# IE_ARSA_Merah_W.net
KiCad netlist of a schematic drawn in EAGLE
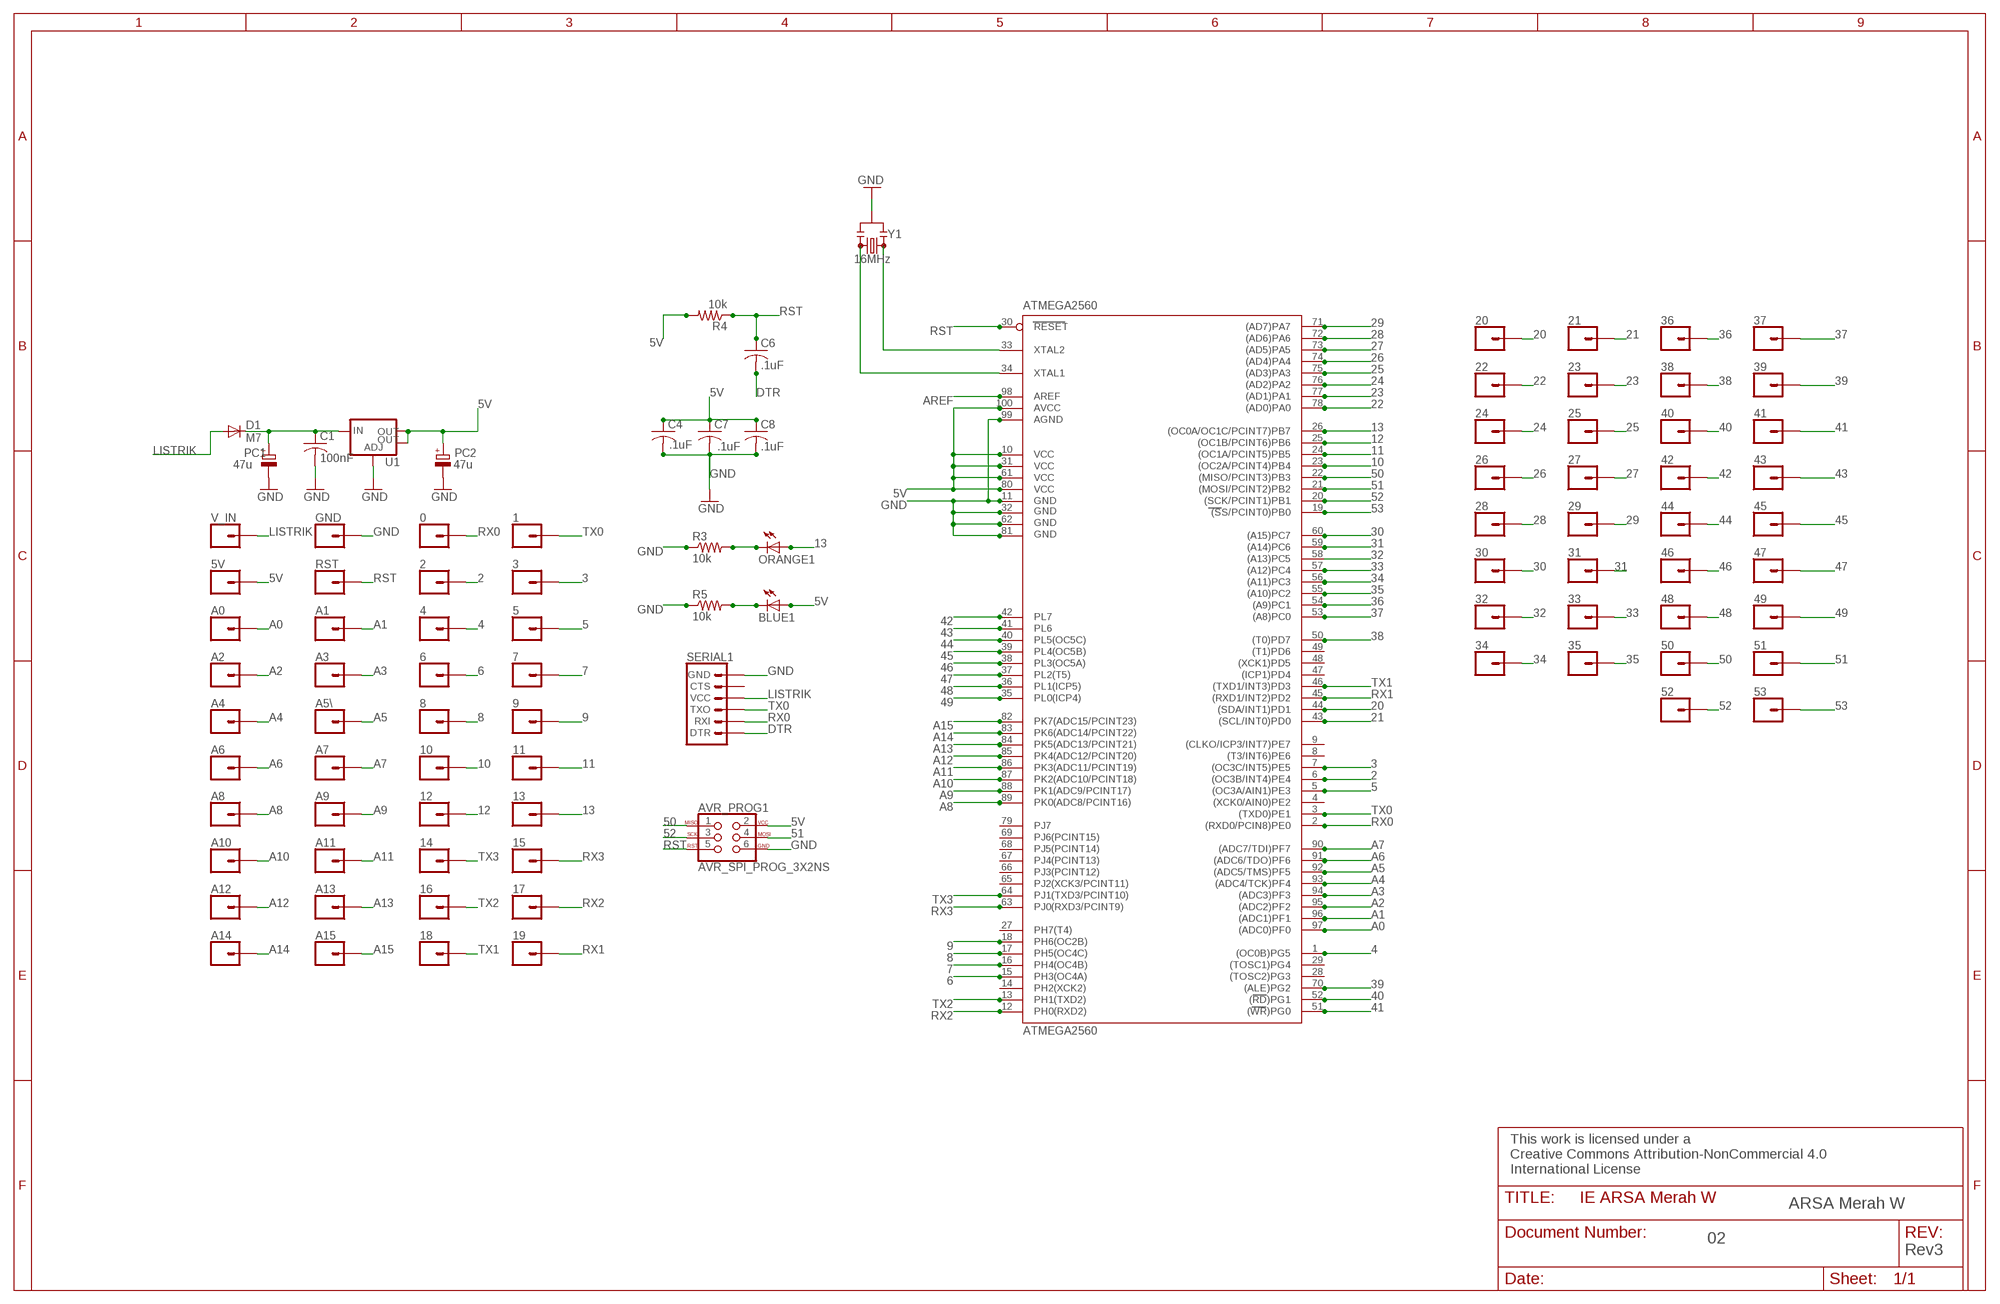
[diagram p0: schematic, sheet 1]

(export (version "E")
  (design (tool "Eeschema 10.0.6"))
  (components
    (comp (ref "0")
      (value "CONN_01")
      (footprint "eagle-import:1X01")
      (libsource (lib "eagle-import") (part "CONN_01"))
    )
    (comp (ref "1")
      (value "CONN_01")
      (footprint "eagle-import:1X01")
      (libsource (lib "eagle-import") (part "CONN_01"))
    )
    (comp (ref "2")
      (value "CONN_01")
      (footprint "eagle-import:1X01")
      (libsource (lib "eagle-import") (part "CONN_01"))
    )
    (comp (ref "3")
      (value "CONN_01")
      (footprint "eagle-import:1X01")
      (libsource (lib "eagle-import") (part "CONN_01"))
    )
    (comp (ref "4")
      (value "CONN_01")
      (footprint "eagle-import:1X01")
      (libsource (lib "eagle-import") (part "CONN_01"))
    )
    (comp (ref "5")
      (value "CONN_01")
      (footprint "eagle-import:1X01")
      (libsource (lib "eagle-import") (part "CONN_01"))
    )
    (comp (ref "5V")
      (value "CONN_01")
      (footprint "eagle-import:1X01")
      (libsource (lib "eagle-import") (part "CONN_01"))
    )
    (comp (ref "6")
      (value "CONN_01")
      (footprint "eagle-import:1X01")
      (libsource (lib "eagle-import") (part "CONN_01"))
    )
    (comp (ref "7")
      (value "CONN_01")
      (footprint "eagle-import:1X01")
      (libsource (lib "eagle-import") (part "CONN_01"))
    )
    (comp (ref "8")
      (value "CONN_01")
      (footprint "eagle-import:1X01")
      (libsource (lib "eagle-import") (part "CONN_01"))
    )
    (comp (ref "9")
      (value "CONN_01")
      (footprint "eagle-import:1X01")
      (libsource (lib "eagle-import") (part "CONN_01"))
    )
    (comp (ref "10")
      (value "CONN_01")
      (footprint "eagle-import:1X01")
      (libsource (lib "eagle-import") (part "CONN_01"))
    )
    (comp (ref "11")
      (value "CONN_01")
      (footprint "eagle-import:1X01")
      (libsource (lib "eagle-import") (part "CONN_01"))
    )
    (comp (ref "12")
      (value "CONN_01")
      (footprint "eagle-import:1X01")
      (libsource (lib "eagle-import") (part "CONN_01"))
    )
    (comp (ref "13")
      (value "CONN_01")
      (footprint "eagle-import:1X01")
      (libsource (lib "eagle-import") (part "CONN_01"))
    )
    (comp (ref "14")
      (value "CONN_01")
      (footprint "eagle-import:1X01")
      (libsource (lib "eagle-import") (part "CONN_01"))
    )
    (comp (ref "15")
      (value "CONN_01")
      (footprint "eagle-import:1X01")
      (libsource (lib "eagle-import") (part "CONN_01"))
    )
    (comp (ref "16")
      (value "CONN_01")
      (footprint "eagle-import:1X01")
      (libsource (lib "eagle-import") (part "CONN_01"))
    )
    (comp (ref "17")
      (value "CONN_01")
      (footprint "eagle-import:1X01")
      (libsource (lib "eagle-import") (part "CONN_01"))
    )
    (comp (ref "18")
      (value "CONN_01")
      (footprint "eagle-import:1X01")
      (libsource (lib "eagle-import") (part "CONN_01"))
    )
    (comp (ref "19")
      (value "CONN_01")
      (footprint "eagle-import:1X01")
      (libsource (lib "eagle-import") (part "CONN_01"))
    )
    (comp (ref "20")
      (value "CONN_01")
      (footprint "eagle-import:1X01")
      (libsource (lib "eagle-import") (part "CONN_01"))
    )
    (comp (ref "21")
      (value "CONN_01")
      (footprint "eagle-import:1X01")
      (libsource (lib "eagle-import") (part "CONN_01"))
    )
    (comp (ref "22")
      (value "CONN_01")
      (footprint "eagle-import:1X01")
      (libsource (lib "eagle-import") (part "CONN_01"))
    )
    (comp (ref "23")
      (value "CONN_01")
      (footprint "eagle-import:1X01")
      (libsource (lib "eagle-import") (part "CONN_01"))
    )
    (comp (ref "24")
      (value "CONN_01")
      (footprint "eagle-import:1X01")
      (libsource (lib "eagle-import") (part "CONN_01"))
    )
    (comp (ref "25")
      (value "CONN_01")
      (footprint "eagle-import:1X01")
      (libsource (lib "eagle-import") (part "CONN_01"))
    )
    (comp (ref "26")
      (value "CONN_01")
      (footprint "eagle-import:1X01")
      (libsource (lib "eagle-import") (part "CONN_01"))
    )
    (comp (ref "27")
      (value "CONN_01")
      (footprint "eagle-import:1X01")
      (libsource (lib "eagle-import") (part "CONN_01"))
    )
    (comp (ref "28")
      (value "CONN_01")
      (footprint "eagle-import:1X01")
      (libsource (lib "eagle-import") (part "CONN_01"))
    )
    (comp (ref "29")
      (value "CONN_01")
      (footprint "eagle-import:1X01")
      (libsource (lib "eagle-import") (part "CONN_01"))
    )
    (comp (ref "30")
      (value "CONN_01")
      (footprint "eagle-import:1X01")
      (libsource (lib "eagle-import") (part "CONN_01"))
    )
    (comp (ref "31")
      (value "CONN_01")
      (footprint "eagle-import:1X01")
      (libsource (lib "eagle-import") (part "CONN_01"))
    )
    (comp (ref "32")
      (value "CONN_01")
      (footprint "eagle-import:1X01")
      (libsource (lib "eagle-import") (part "CONN_01"))
    )
    (comp (ref "33")
      (value "CONN_01")
      (footprint "eagle-import:1X01")
      (libsource (lib "eagle-import") (part "CONN_01"))
    )
    (comp (ref "34")
      (value "CONN_01")
      (footprint "eagle-import:1X01")
      (libsource (lib "eagle-import") (part "CONN_01"))
    )
    (comp (ref "35")
      (value "CONN_01")
      (footprint "eagle-import:1X01")
      (libsource (lib "eagle-import") (part "CONN_01"))
    )
    (comp (ref "36")
      (value "CONN_01")
      (footprint "eagle-import:1X01")
      (libsource (lib "eagle-import") (part "CONN_01"))
    )
    (comp (ref "37")
      (value "CONN_01")
      (footprint "eagle-import:1X01")
      (libsource (lib "eagle-import") (part "CONN_01"))
    )
    (comp (ref "38")
      (value "CONN_01")
      (footprint "eagle-import:1X01")
      (libsource (lib "eagle-import") (part "CONN_01"))
    )
    (comp (ref "39")
      (value "CONN_01")
      (footprint "eagle-import:1X01")
      (libsource (lib "eagle-import") (part "CONN_01"))
    )
    (comp (ref "40")
      (value "CONN_01")
      (footprint "eagle-import:1X01")
      (libsource (lib "eagle-import") (part "CONN_01"))
    )
    (comp (ref "41")
      (value "CONN_01")
      (footprint "eagle-import:1X01")
      (libsource (lib "eagle-import") (part "CONN_01"))
    )
    (comp (ref "42")
      (value "CONN_01")
      (footprint "eagle-import:1X01")
      (libsource (lib "eagle-import") (part "CONN_01"))
    )
    (comp (ref "43")
      (value "CONN_01")
      (footprint "eagle-import:1X01")
      (libsource (lib "eagle-import") (part "CONN_01"))
    )
    (comp (ref "44")
      (value "CONN_01")
      (footprint "eagle-import:1X01")
      (libsource (lib "eagle-import") (part "CONN_01"))
    )
    (comp (ref "45")
      (value "CONN_01")
      (footprint "eagle-import:1X01")
      (libsource (lib "eagle-import") (part "CONN_01"))
    )
    (comp (ref "46")
      (value "CONN_01")
      (footprint "eagle-import:1X01")
      (libsource (lib "eagle-import") (part "CONN_01"))
    )
    (comp (ref "47")
      (value "CONN_01")
      (footprint "eagle-import:1X01")
      (libsource (lib "eagle-import") (part "CONN_01"))
    )
    (comp (ref "48")
      (value "CONN_01")
      (footprint "eagle-import:1X01")
      (libsource (lib "eagle-import") (part "CONN_01"))
    )
    (comp (ref "49")
      (value "CONN_01")
      (footprint "eagle-import:1X01")
      (libsource (lib "eagle-import") (part "CONN_01"))
    )
    (comp (ref "50")
      (value "CONN_01")
      (footprint "eagle-import:1X01")
      (libsource (lib "eagle-import") (part "CONN_01"))
    )
    (comp (ref "51")
      (value "CONN_01")
      (footprint "eagle-import:1X01")
      (libsource (lib "eagle-import") (part "CONN_01"))
    )
    (comp (ref "52")
      (value "CONN_01")
      (footprint "eagle-import:1X01")
      (libsource (lib "eagle-import") (part "CONN_01"))
    )
    (comp (ref "53")
      (value "CONN_01")
      (footprint "eagle-import:1X01")
      (libsource (lib "eagle-import") (part "CONN_01"))
    )
    (comp (ref "A0")
      (value "CONN_01")
      (footprint "eagle-import:1X01")
      (libsource (lib "eagle-import") (part "CONN_01"))
    )
    (comp (ref "A1")
      (value "CONN_01")
      (footprint "eagle-import:1X01")
      (libsource (lib "eagle-import") (part "CONN_01"))
    )
    (comp (ref "A2")
      (value "CONN_01")
      (footprint "eagle-import:1X01")
      (libsource (lib "eagle-import") (part "CONN_01"))
    )
    (comp (ref "A3")
      (value "CONN_01")
      (footprint "eagle-import:1X01")
      (libsource (lib "eagle-import") (part "CONN_01"))
    )
    (comp (ref "A4")
      (value "CONN_01")
      (footprint "eagle-import:1X01")
      (libsource (lib "eagle-import") (part "CONN_01"))
    )
    (comp (ref "A5\\")
      (value "CONN_01")
      (footprint "eagle-import:1X01")
      (libsource (lib "eagle-import") (part "CONN_01"))
    )
    (comp (ref "A6")
      (value "CONN_01")
      (footprint "eagle-import:1X01")
      (libsource (lib "eagle-import") (part "CONN_01"))
    )
    (comp (ref "A7")
      (value "CONN_01")
      (footprint "eagle-import:1X01")
      (libsource (lib "eagle-import") (part "CONN_01"))
    )
    (comp (ref "A8")
      (value "CONN_01")
      (footprint "eagle-import:1X01")
      (libsource (lib "eagle-import") (part "CONN_01"))
    )
    (comp (ref "A9")
      (value "CONN_01")
      (footprint "eagle-import:1X01")
      (libsource (lib "eagle-import") (part "CONN_01"))
    )
    (comp (ref "A10")
      (value "CONN_01")
      (footprint "eagle-import:1X01")
      (libsource (lib "eagle-import") (part "CONN_01"))
    )
    (comp (ref "A11")
      (value "CONN_01")
      (footprint "eagle-import:1X01")
      (libsource (lib "eagle-import") (part "CONN_01"))
    )
    (comp (ref "A12")
      (value "CONN_01")
      (footprint "eagle-import:1X01")
      (libsource (lib "eagle-import") (part "CONN_01"))
    )
    (comp (ref "A13")
      (value "CONN_01")
      (footprint "eagle-import:1X01")
      (libsource (lib "eagle-import") (part "CONN_01"))
    )
    (comp (ref "A14")
      (value "CONN_01")
      (footprint "eagle-import:1X01")
      (libsource (lib "eagle-import") (part "CONN_01"))
    )
    (comp (ref "A15")
      (value "CONN_01")
      (footprint "eagle-import:1X01")
      (libsource (lib "eagle-import") (part "CONN_01"))
    )
    (comp (ref "ATMEGA2560")
      (value "ATMEGA2560")
      (footprint "eagle-import:TQFP100")
      (libsource (lib "eagle-import") (part "ATMEGA2560"))
    )
    (comp (ref "AVR_PROG1")
      (value "AVR_SPI_PROG_3X2NS")
      (footprint "eagle-import:2X3-NS")
      (libsource (lib "eagle-import") (part "AVR_SPI_PROG_3X2NS"))
    )
    (comp (ref "BLUE1")
      (value "L")
      (footprint "eagle-import:SMD-0805-LED")
      (libsource (lib "eagle-import") (part "LED-SMD-0805"))
    )
    (comp (ref "C1")
      (value "100nF")
      (footprint "eagle-import:SMD-0805")
      (libsource (lib "eagle-import") (part "CAPACITOR-SMD-0805"))
    )
    (comp (ref "C4")
      (value "CAPACITOR-SMD-0805")
      (footprint "eagle-import:SMD-0805")
      (libsource (lib "eagle-import") (part "CAPACITOR-SMD-0805"))
    )
    (comp (ref "C6")
      (value ".1uF")
      (footprint "eagle-import:SMD-0805")
      (libsource (lib "eagle-import") (part "CAPACITOR-SMD-0805"))
    )
    (comp (ref "C7")
      (value ".1uF")
      (footprint "eagle-import:SMD-0805")
      (libsource (lib "eagle-import") (part "CAPACITOR-SMD-0805"))
    )
    (comp (ref "C8")
      (value ".1uF")
      (footprint "eagle-import:SMD-0805")
      (libsource (lib "eagle-import") (part "CAPACITOR-SMD-0805"))
    )
    (comp (ref "D1")
      (value "M7")
      (footprint "eagle-import:SMB")
      (libsource (lib "eagle-import") (part "DIODE-SMB"))
    )
    (comp (ref "GND")
      (value "CONN_01")
      (footprint "eagle-import:1X01")
      (libsource (lib "eagle-import") (part "CONN_01"))
    )
    (comp (ref "ORANGE1")
      (value "L")
      (footprint "eagle-import:SMD-0805-LED")
      (libsource (lib "eagle-import") (part "LED-SMD-0805"))
    )
    (comp (ref "PC1")
      (value "47u")
      (footprint "eagle-import:PANASONIC_D")
      (libsource (lib "eagle-import") (part "CPOL-EUD"))
    )
    (comp (ref "PC2")
      (value "47u")
      (footprint "eagle-import:PANASONIC_D")
      (libsource (lib "eagle-import") (part "CPOL-EUD"))
    )
    (comp (ref "R3")
      (value "10k")
      (footprint "eagle-import:SMD-0805")
      (libsource (lib "eagle-import") (part "RESISTOR-SMD-0805"))
    )
    (comp (ref "R4")
      (value "10k")
      (footprint "eagle-import:SMD-0805")
      (libsource (lib "eagle-import") (part "RESISTOR-SMD-0805"))
    )
    (comp (ref "R5")
      (value "10k")
      (footprint "eagle-import:SMD-0805")
      (libsource (lib "eagle-import") (part "RESISTOR-SMD-0805"))
    )
    (comp (ref "RST")
      (value "CONN_01")
      (footprint "eagle-import:1X01")
      (libsource (lib "eagle-import") (part "CONN_01"))
    )
    (comp (ref "SERIAL1")
      (value "6_PIN_SERIAL_TARGET")
      (footprint "eagle-import:1X06")
      (libsource (lib "eagle-import") (part "6_PIN_SERIAL_TARGET"))
    )
    (comp (ref "U1")
      (value "V_REG_LM1117SOT223")
      (footprint "eagle-import:SOT223")
      (libsource (lib "eagle-import") (part "V_REG_LM1117SOT223"))
    )
    (comp (ref "V_IN")
      (value "CONN_01")
      (footprint "eagle-import:1X01")
      (libsource (lib "eagle-import") (part "CONN_01"))
    )
    (comp (ref "Y1")
      (value "16MHz")
      (footprint "eagle-import:RESONATOR-SMD-3.2X1.3")
      (libsource (lib "eagle-import") (part "RESONATOR-16MHZSMD_3.2X1.3"))
    )
  )
  (nets
    (net (code "1") (name "/LISTRIK") (class "Default")
      (node (ref "D1") (pin "A") (pinfunction "A_A") (pintype "passive"))
      (node (ref "SERIAL1") (pin "4") (pinfunction "VCC_4") (pintype "passive"))
      (node (ref "V_IN") (pin "1") (pinfunction "1_1") (pintype "passive"))
    )
    (net (code "2") (name "2") (class "Default")
      (node (ref "2") (pin "1") (pinfunction "1_1") (pintype "passive"))
      (node (ref "ATMEGA2560") (pin "6") (pinfunction "(OC3B/INT4)PE4_6") (pintype "bidirectional"))
    )
    (net (code "3") (name "3") (class "Default")
      (node (ref "3") (pin "1") (pinfunction "1_1") (pintype "passive"))
      (node (ref "ATMEGA2560") (pin "7") (pinfunction "(OC3C/INT5)PE5_7") (pintype "bidirectional"))
    )
    (net (code "4") (name "4") (class "Default")
      (node (ref "4") (pin "1") (pinfunction "1_1") (pintype "passive"))
      (node (ref "ATMEGA2560") (pin "1") (pinfunction "(OC0B)PG5_1") (pintype "bidirectional"))
    )
    (net (code "5") (name "5") (class "Default")
      (node (ref "5") (pin "1") (pinfunction "1_1") (pintype "passive"))
      (node (ref "ATMEGA2560") (pin "5") (pinfunction "(OC3A/AIN1)PE3_5") (pintype "bidirectional"))
    )
    (net (code "6") (name "5V") (class "Default")
      (node (ref "5V") (pin "1") (pinfunction "1_1") (pintype "passive"))
      (node (ref "ATMEGA2560") (pin "10") (pinfunction "VCC_10") (pintype "power_in"))
      (node (ref "ATMEGA2560") (pin "100") (pinfunction "AVCC_100") (pintype "power_in"))
      (node (ref "ATMEGA2560") (pin "31") (pinfunction "VCC1_31") (pintype "power_in"))
      (node (ref "ATMEGA2560") (pin "61") (pinfunction "VCC2_61") (pintype "power_in"))
      (node (ref "ATMEGA2560") (pin "80") (pinfunction "VCC3_80") (pintype "power_in"))
      (node (ref "AVR_PROG1") (pin "2") (pinfunction "2_2") (pintype "passive"))
      (node (ref "BLUE1") (pin "1") (pinfunction "A_1") (pintype "passive"))
      (node (ref "C4") (pin "1") (pinfunction "1_1") (pintype "passive"))
      (node (ref "C7") (pin "1") (pinfunction "1_1") (pintype "passive"))
      (node (ref "C8") (pin "1") (pinfunction "1_1") (pintype "passive"))
      (node (ref "PC2") (pin "+") (pinfunction "+_+") (pintype "passive"))
      (node (ref "R4") (pin "2") (pinfunction "2_2") (pintype "passive"))
      (node (ref "U1") (pin "2") (pinfunction "OUT_2") (pintype "output"))
      (node (ref "U1") (pin "4") (pinfunction "OUT_4") (pintype "output"))
    )
    (net (code "7") (name "6") (class "Default")
      (node (ref "6") (pin "1") (pinfunction "1_1") (pintype "passive"))
      (node (ref "ATMEGA2560") (pin "15") (pinfunction "PH3(OC4A)_15") (pintype "bidirectional"))
    )
    (net (code "8") (name "7") (class "Default")
      (node (ref "7") (pin "1") (pinfunction "1_1") (pintype "passive"))
      (node (ref "ATMEGA2560") (pin "16") (pinfunction "PH4(OC4B)_16") (pintype "bidirectional"))
    )
    (net (code "9") (name "8") (class "Default")
      (node (ref "8") (pin "1") (pinfunction "1_1") (pintype "passive"))
      (node (ref "ATMEGA2560") (pin "17") (pinfunction "PH5(OC4C)_17") (pintype "bidirectional"))
    )
    (net (code "10") (name "9") (class "Default")
      (node (ref "9") (pin "1") (pinfunction "1_1") (pintype "passive"))
      (node (ref "ATMEGA2560") (pin "18") (pinfunction "PH6(OC2B)_18") (pintype "bidirectional"))
    )
    (net (code "11") (name "10") (class "Default")
      (node (ref "10") (pin "1") (pinfunction "1_1") (pintype "passive"))
      (node (ref "ATMEGA2560") (pin "23") (pinfunction "(OC2A/PCINT4)PB4_23") (pintype "bidirectional"))
    )
    (net (code "12") (name "11") (class "Default")
      (node (ref "11") (pin "1") (pinfunction "1_1") (pintype "passive"))
      (node (ref "ATMEGA2560") (pin "24") (pinfunction "(OC1A/PCINT5)PB5_24") (pintype "bidirectional"))
    )
    (net (code "13") (name "12") (class "Default")
      (node (ref "12") (pin "1") (pinfunction "1_1") (pintype "passive"))
      (node (ref "ATMEGA2560") (pin "25") (pinfunction "(OC1B/PCINT6)PB6_25") (pintype "bidirectional"))
    )
    (net (code "14") (name "13") (class "Default")
      (node (ref "13") (pin "1") (pinfunction "1_1") (pintype "passive"))
      (node (ref "ATMEGA2560") (pin "26") (pinfunction "(OC0A/OC1C/PCINT7)PB7_26") (pintype "bidirectional"))
      (node (ref "ORANGE1") (pin "1") (pinfunction "A_1") (pintype "passive"))
    )
    (net (code "15") (name "20") (class "Default")
      (node (ref "20") (pin "1") (pinfunction "1_1") (pintype "passive"))
      (node (ref "ATMEGA2560") (pin "44") (pinfunction "(SDA/INT1)PD1_44") (pintype "bidirectional"))
    )
    (net (code "16") (name "21") (class "Default")
      (node (ref "21") (pin "1") (pinfunction "1_1") (pintype "passive"))
      (node (ref "ATMEGA2560") (pin "43") (pinfunction "(SCL/INT0)PD0_43") (pintype "bidirectional"))
    )
    (net (code "17") (name "22") (class "Default")
      (node (ref "22") (pin "1") (pinfunction "1_1") (pintype "passive"))
      (node (ref "ATMEGA2560") (pin "78") (pinfunction "(AD0)PA0_78") (pintype "bidirectional"))
    )
    (net (code "18") (name "23") (class "Default")
      (node (ref "23") (pin "1") (pinfunction "1_1") (pintype "passive"))
      (node (ref "ATMEGA2560") (pin "77") (pinfunction "(AD1)PA1_77") (pintype "bidirectional"))
    )
    (net (code "19") (name "24") (class "Default")
      (node (ref "24") (pin "1") (pinfunction "1_1") (pintype "passive"))
      (node (ref "ATMEGA2560") (pin "76") (pinfunction "(AD2)PA2_76") (pintype "bidirectional"))
    )
    (net (code "20") (name "25") (class "Default")
      (node (ref "25") (pin "1") (pinfunction "1_1") (pintype "passive"))
      (node (ref "ATMEGA2560") (pin "75") (pinfunction "(AD3)PA3_75") (pintype "bidirectional"))
    )
    (net (code "21") (name "26") (class "Default")
      (node (ref "26") (pin "1") (pinfunction "1_1") (pintype "passive"))
      (node (ref "ATMEGA2560") (pin "74") (pinfunction "(AD4)PA4_74") (pintype "bidirectional"))
    )
    (net (code "22") (name "27") (class "Default")
      (node (ref "27") (pin "1") (pinfunction "1_1") (pintype "passive"))
      (node (ref "ATMEGA2560") (pin "73") (pinfunction "(AD5)PA5_73") (pintype "bidirectional"))
    )
    (net (code "23") (name "28") (class "Default")
      (node (ref "28") (pin "1") (pinfunction "1_1") (pintype "passive"))
      (node (ref "ATMEGA2560") (pin "72") (pinfunction "(AD6)PA6_72") (pintype "bidirectional"))
    )
    (net (code "24") (name "29") (class "Default")
      (node (ref "29") (pin "1") (pinfunction "1_1") (pintype "passive"))
      (node (ref "ATMEGA2560") (pin "71") (pinfunction "(AD7)PA7_71") (pintype "bidirectional"))
    )
    (net (code "25") (name "30") (class "Default")
      (node (ref "30") (pin "1") (pinfunction "1_1") (pintype "passive"))
      (node (ref "ATMEGA2560") (pin "60") (pinfunction "(A15)PC7_60") (pintype "bidirectional"))
    )
    (net (code "26") (name "31") (class "Default")
      (node (ref "31") (pin "1") (pinfunction "1_1") (pintype "passive"))
      (node (ref "ATMEGA2560") (pin "59") (pinfunction "(A14)PC6_59") (pintype "bidirectional"))
    )
    (net (code "27") (name "32") (class "Default")
      (node (ref "32") (pin "1") (pinfunction "1_1") (pintype "passive"))
      (node (ref "ATMEGA2560") (pin "58") (pinfunction "(A13)PC5_58") (pintype "bidirectional"))
    )
    (net (code "28") (name "33") (class "Default")
      (node (ref "33") (pin "1") (pinfunction "1_1") (pintype "passive"))
      (node (ref "ATMEGA2560") (pin "57") (pinfunction "(A12)PC4_57") (pintype "bidirectional"))
    )
    (net (code "29") (name "34") (class "Default")
      (node (ref "34") (pin "1") (pinfunction "1_1") (pintype "passive"))
      (node (ref "ATMEGA2560") (pin "56") (pinfunction "(A11)PC3_56") (pintype "bidirectional"))
    )
    (net (code "30") (name "35") (class "Default")
      (node (ref "35") (pin "1") (pinfunction "1_1") (pintype "passive"))
      (node (ref "ATMEGA2560") (pin "55") (pinfunction "(A10)PC2_55") (pintype "bidirectional"))
    )
    (net (code "31") (name "36") (class "Default")
      (node (ref "36") (pin "1") (pinfunction "1_1") (pintype "passive"))
      (node (ref "ATMEGA2560") (pin "54") (pinfunction "(A9)PC1_54") (pintype "bidirectional"))
    )
    (net (code "32") (name "37") (class "Default")
      (node (ref "37") (pin "1") (pinfunction "1_1") (pintype "passive"))
      (node (ref "ATMEGA2560") (pin "53") (pinfunction "(A8)PC0_53") (pintype "bidirectional"))
    )
    (net (code "33") (name "38") (class "Default")
      (node (ref "38") (pin "1") (pinfunction "1_1") (pintype "passive"))
      (node (ref "ATMEGA2560") (pin "50") (pinfunction "(T0)PD7_50") (pintype "bidirectional"))
    )
    (net (code "34") (name "39") (class "Default")
      (node (ref "39") (pin "1") (pinfunction "1_1") (pintype "passive"))
      (node (ref "ATMEGA2560") (pin "70") (pinfunction "(ALE)PG2_70") (pintype "bidirectional"))
    )
    (net (code "35") (name "40") (class "Default")
      (node (ref "40") (pin "1") (pinfunction "1_1") (pintype "passive"))
      (node (ref "ATMEGA2560") (pin "52") (pinfunction "(RD)PG1_52") (pintype "bidirectional"))
    )
    (net (code "36") (name "41") (class "Default")
      (node (ref "41") (pin "1") (pinfunction "1_1") (pintype "passive"))
      (node (ref "ATMEGA2560") (pin "51") (pinfunction "(WR)PG0_51") (pintype "bidirectional"))
    )
    (net (code "37") (name "42") (class "Default")
      (node (ref "42") (pin "1") (pinfunction "1_1") (pintype "passive"))
      (node (ref "ATMEGA2560") (pin "42") (pinfunction "PL7_42") (pintype "bidirectional"))
    )
    (net (code "38") (name "43") (class "Default")
      (node (ref "43") (pin "1") (pinfunction "1_1") (pintype "passive"))
      (node (ref "ATMEGA2560") (pin "41") (pinfunction "PL6_41") (pintype "bidirectional"))
    )
    (net (code "39") (name "44") (class "Default")
      (node (ref "44") (pin "1") (pinfunction "1_1") (pintype "passive"))
      (node (ref "ATMEGA2560") (pin "40") (pinfunction "PL5(OC5C)_40") (pintype "bidirectional"))
    )
    (net (code "40") (name "45") (class "Default")
      (node (ref "45") (pin "1") (pinfunction "1_1") (pintype "passive"))
      (node (ref "ATMEGA2560") (pin "39") (pinfunction "PL4(OC5B)_39") (pintype "bidirectional"))
    )
    (net (code "41") (name "46") (class "Default")
      (node (ref "46") (pin "1") (pinfunction "1_1") (pintype "passive"))
      (node (ref "ATMEGA2560") (pin "38") (pinfunction "PL3(OC5A)_38") (pintype "bidirectional"))
    )
    (net (code "42") (name "47") (class "Default")
      (node (ref "47") (pin "1") (pinfunction "1_1") (pintype "passive"))
      (node (ref "ATMEGA2560") (pin "37") (pinfunction "PL2(T5)_37") (pintype "bidirectional"))
    )
    (net (code "43") (name "48") (class "Default")
      (node (ref "48") (pin "1") (pinfunction "1_1") (pintype "passive"))
      (node (ref "ATMEGA2560") (pin "36") (pinfunction "PL1(ICP5)_36") (pintype "bidirectional"))
    )
    (net (code "44") (name "49") (class "Default")
      (node (ref "49") (pin "1") (pinfunction "1_1") (pintype "passive"))
      (node (ref "ATMEGA2560") (pin "35") (pinfunction "PL0(ICP4)_35") (pintype "bidirectional"))
    )
    (net (code "45") (name "50") (class "Default")
      (node (ref "50") (pin "1") (pinfunction "1_1") (pintype "passive"))
      (node (ref "ATMEGA2560") (pin "22") (pinfunction "(MISO/PCINT3)PB3_22") (pintype "bidirectional"))
      (node (ref "AVR_PROG1") (pin "1") (pinfunction "1_1") (pintype "passive"))
    )
    (net (code "46") (name "51") (class "Default")
      (node (ref "51") (pin "1") (pinfunction "1_1") (pintype "passive"))
      (node (ref "ATMEGA2560") (pin "21") (pinfunction "(MOSI/PCINT2)PB2_21") (pintype "bidirectional"))
      (node (ref "AVR_PROG1") (pin "4") (pinfunction "4_4") (pintype "passive"))
    )
    (net (code "47") (name "52") (class "Default")
      (node (ref "52") (pin "1") (pinfunction "1_1") (pintype "passive"))
      (node (ref "ATMEGA2560") (pin "20") (pinfunction "(SCK/PCINT1)PB1_20") (pintype "bidirectional"))
      (node (ref "AVR_PROG1") (pin "3") (pinfunction "3_3") (pintype "passive"))
    )
    (net (code "48") (name "53") (class "Default")
      (node (ref "53") (pin "1") (pinfunction "1_1") (pintype "passive"))
      (node (ref "ATMEGA2560") (pin "19") (pinfunction "(SS/PCINT0)PB0_19") (pintype "bidirectional"))
    )
    (net (code "49") (name "A0") (class "Default")
      (node (ref "A0") (pin "1") (pinfunction "1_1") (pintype "passive"))
      (node (ref "ATMEGA2560") (pin "97") (pinfunction "(ADC0)PF0_97") (pintype "bidirectional"))
    )
    (net (code "50") (name "A1") (class "Default")
      (node (ref "A1") (pin "1") (pinfunction "1_1") (pintype "passive"))
      (node (ref "ATMEGA2560") (pin "96") (pinfunction "(ADC1)PF1_96") (pintype "bidirectional"))
    )
    (net (code "51") (name "A2") (class "Default")
      (node (ref "A2") (pin "1") (pinfunction "1_1") (pintype "passive"))
      (node (ref "ATMEGA2560") (pin "95") (pinfunction "(ADC2)PF2_95") (pintype "bidirectional"))
    )
    (net (code "52") (name "A3") (class "Default")
      (node (ref "A3") (pin "1") (pinfunction "1_1") (pintype "passive"))
      (node (ref "ATMEGA2560") (pin "94") (pinfunction "(ADC3)PF3_94") (pintype "bidirectional"))
    )
    (net (code "53") (name "A4") (class "Default")
      (node (ref "A4") (pin "1") (pinfunction "1_1") (pintype "passive"))
      (node (ref "ATMEGA2560") (pin "93") (pinfunction "(ADC4/TCK)PF4_93") (pintype "bidirectional"))
    )
    (net (code "54") (name "A5") (class "Default")
      (node (ref "A5\\") (pin "1") (pinfunction "1_1") (pintype "passive"))
      (node (ref "ATMEGA2560") (pin "92") (pinfunction "(ADC5/TMS)PF5_92") (pintype "bidirectional"))
    )
    (net (code "55") (name "A6") (class "Default")
      (node (ref "A6") (pin "1") (pinfunction "1_1") (pintype "passive"))
      (node (ref "ATMEGA2560") (pin "91") (pinfunction "(ADC6/TDO)PF6_91") (pintype "bidirectional"))
    )
    (net (code "56") (name "A7") (class "Default")
      (node (ref "A7") (pin "1") (pinfunction "1_1") (pintype "passive"))
      (node (ref "ATMEGA2560") (pin "90") (pinfunction "(ADC7/TDI)PF7_90") (pintype "bidirectional"))
    )
    (net (code "57") (name "A8") (class "Default")
      (node (ref "A8") (pin "1") (pinfunction "1_1") (pintype "passive"))
      (node (ref "ATMEGA2560") (pin "89") (pinfunction "PK0(ADC8/PCINT16)_89") (pintype "bidirectional"))
    )
    (net (code "58") (name "A9") (class "Default")
      (node (ref "A9") (pin "1") (pinfunction "1_1") (pintype "passive"))
      (node (ref "ATMEGA2560") (pin "88") (pinfunction "PK1(ADC9/PCINT17)_88") (pintype "bidirectional"))
    )
    (net (code "59") (name "A10") (class "Default")
      (node (ref "A10") (pin "1") (pinfunction "1_1") (pintype "passive"))
      (node (ref "ATMEGA2560") (pin "87") (pinfunction "PK2(ADC10/PCINT18)_87") (pintype "bidirectional"))
    )
    (net (code "60") (name "A11") (class "Default")
      (node (ref "A11") (pin "1") (pinfunction "1_1") (pintype "passive"))
      (node (ref "ATMEGA2560") (pin "86") (pinfunction "PK3(ADC11/PCINT19)_86") (pintype "bidirectional"))
    )
    (net (code "61") (name "A12") (class "Default")
      (node (ref "A12") (pin "1") (pinfunction "1_1") (pintype "passive"))
      (node (ref "ATMEGA2560") (pin "85") (pinfunction "PK4(ADC12/PCINT20)_85") (pintype "bidirectional"))
    )
    (net (code "62") (name "A13") (class "Default")
      (node (ref "A13") (pin "1") (pinfunction "1_1") (pintype "passive"))
      (node (ref "ATMEGA2560") (pin "84") (pinfunction "PK5(ADC13/PCINT21)_84") (pintype "bidirectional"))
    )
    (net (code "63") (name "A14") (class "Default")
      (node (ref "A14") (pin "1") (pinfunction "1_1") (pintype "passive"))
      (node (ref "ATMEGA2560") (pin "83") (pinfunction "PK6(ADC14/PCINT22)_83") (pintype "bidirectional"))
    )
    (net (code "64") (name "A15") (class "Default")
      (node (ref "A15") (pin "1") (pinfunction "1_1") (pintype "passive"))
      (node (ref "ATMEGA2560") (pin "82") (pinfunction "PK7(ADC15/PCINT23)_82") (pintype "bidirectional"))
    )
    (net (code "65") (name "AREF") (class "Default")
      (node (ref "ATMEGA2560") (pin "98") (pinfunction "AREF_98") (pintype "bidirectional"))
    )
    (net (code "66") (name "DTR") (class "Default")
      (node (ref "C6") (pin "2") (pinfunction "2_2") (pintype "passive"))
      (node (ref "SERIAL1") (pin "1") (pinfunction "DTR_1") (pintype "passive"))
    )
    (net (code "67") (name "GND") (class "Default")
      (node (ref "ATMEGA2560") (pin "11") (pinfunction "GND_11") (pintype "power_in"))
      (node (ref "ATMEGA2560") (pin "32") (pinfunction "GND1_32") (pintype "power_in"))
      (node (ref "ATMEGA2560") (pin "62") (pinfunction "GND2_62") (pintype "power_in"))
      (node (ref "ATMEGA2560") (pin "81") (pinfunction "GND3_81") (pintype "power_in"))
      (node (ref "ATMEGA2560") (pin "99") (pinfunction "AGND_99") (pintype "power_in"))
      (node (ref "AVR_PROG1") (pin "6") (pinfunction "6_6") (pintype "passive"))
      (node (ref "C1") (pin "2") (pinfunction "2_2") (pintype "passive"))
      (node (ref "C4") (pin "2") (pinfunction "2_2") (pintype "passive"))
      (node (ref "C7") (pin "2") (pinfunction "2_2") (pintype "passive"))
      (node (ref "C8") (pin "2") (pinfunction "2_2") (pintype "passive"))
      (node (ref "GND") (pin "1") (pinfunction "1_1") (pintype "passive"))
      (node (ref "PC1") (pin "-") (pinfunction "-_-") (pintype "passive"))
      (node (ref "PC2") (pin "-") (pinfunction "-_-") (pintype "passive"))
      (node (ref "R3") (pin "1") (pinfunction "1_1") (pintype "passive"))
      (node (ref "R5") (pin "1") (pinfunction "1_1") (pintype "passive"))
      (node (ref "SERIAL1") (pin "6") (pinfunction "GND_6") (pintype "passive"))
      (node (ref "U1") (pin "1") (pinfunction "ADJ_1") (pintype "input"))
      (node (ref "Y1") (pin "2") (pinfunction "2_2") (pintype "passive"))
    )
    (net (code "68") (name "Net-(ATMEGA2560-XTAL1)") (class "Default")
      (node (ref "ATMEGA2560") (pin "34") (pinfunction "XTAL1_34") (pintype "input"))
      (node (ref "Y1") (pin "3") (pinfunction "3_3") (pintype "passive"))
    )
    (net (code "69") (name "Net-(ATMEGA2560-XTAL2)") (class "Default")
      (node (ref "ATMEGA2560") (pin "33") (pinfunction "XTAL2_33") (pintype "output"))
      (node (ref "Y1") (pin "1") (pinfunction "1_1") (pintype "passive"))
    )
    (net (code "70") (name "Net-(BLUE1-C)") (class "Default")
      (node (ref "BLUE1") (pin "2") (pinfunction "C_2") (pintype "passive"))
      (node (ref "R5") (pin "2") (pinfunction "2_2") (pintype "passive"))
    )
    (net (code "71") (name "Net-(ORANGE1-C)") (class "Default")
      (node (ref "ORANGE1") (pin "2") (pinfunction "C_2") (pintype "passive"))
      (node (ref "R3") (pin "2") (pinfunction "2_2") (pintype "passive"))
    )
    (net (code "72") (name "Net-(U1-IN)") (class "Default")
      (node (ref "C1") (pin "1") (pinfunction "1_1") (pintype "passive"))
      (node (ref "D1") (pin "C") (pinfunction "C_C") (pintype "passive"))
      (node (ref "PC1") (pin "+") (pinfunction "+_+") (pintype "passive"))
      (node (ref "U1") (pin "3") (pinfunction "IN_3") (pintype "input"))
    )
    (net (code "73") (name "RST") (class "Default")
      (node (ref "ATMEGA2560") (pin "30") (pinfunction "RESET_30") (pintype "input"))
      (node (ref "AVR_PROG1") (pin "5") (pinfunction "5_5") (pintype "passive"))
      (node (ref "C6") (pin "1") (pinfunction "1_1") (pintype "passive"))
      (node (ref "R4") (pin "1") (pinfunction "1_1") (pintype "passive"))
      (node (ref "RST") (pin "1") (pinfunction "1_1") (pintype "passive"))
    )
    (net (code "74") (name "RX0") (class "Default")
      (node (ref "0") (pin "1") (pinfunction "1_1") (pintype "passive"))
      (node (ref "ATMEGA2560") (pin "2") (pinfunction "(RXD0/PCIN8)PE0_2") (pintype "bidirectional"))
      (node (ref "SERIAL1") (pin "2") (pinfunction "RXI_2") (pintype "passive"))
    )
    (net (code "75") (name "RX1") (class "Default")
      (node (ref "19") (pin "1") (pinfunction "1_1") (pintype "passive"))
      (node (ref "ATMEGA2560") (pin "45") (pinfunction "(RXD1/INT2)PD2_45") (pintype "bidirectional"))
    )
    (net (code "76") (name "RX2") (class "Default")
      (node (ref "17") (pin "1") (pinfunction "1_1") (pintype "passive"))
      (node (ref "ATMEGA2560") (pin "12") (pinfunction "PH0(RXD2)_12") (pintype "bidirectional"))
    )
    (net (code "77") (name "RX3") (class "Default")
      (node (ref "15") (pin "1") (pinfunction "1_1") (pintype "passive"))
      (node (ref "ATMEGA2560") (pin "63") (pinfunction "PJ0(RXD3/PCINT9)_63") (pintype "bidirectional"))
    )
    (net (code "78") (name "TX0") (class "Default")
      (node (ref "1") (pin "1") (pinfunction "1_1") (pintype "passive"))
      (node (ref "ATMEGA2560") (pin "3") (pinfunction "(TXD0)PE1_3") (pintype "bidirectional"))
      (node (ref "SERIAL1") (pin "3") (pinfunction "TXO_3") (pintype "passive"))
    )
    (net (code "79") (name "TX1") (class "Default")
      (node (ref "18") (pin "1") (pinfunction "1_1") (pintype "passive"))
      (node (ref "ATMEGA2560") (pin "46") (pinfunction "(TXD1/INT3)PD3_46") (pintype "bidirectional"))
    )
    (net (code "80") (name "TX2") (class "Default")
      (node (ref "16") (pin "1") (pinfunction "1_1") (pintype "passive"))
      (node (ref "ATMEGA2560") (pin "13") (pinfunction "PH1(TXD2)_13") (pintype "bidirectional"))
    )
    (net (code "81") (name "TX3") (class "Default")
      (node (ref "14") (pin "1") (pinfunction "1_1") (pintype "passive"))
      (node (ref "ATMEGA2560") (pin "64") (pinfunction "PJ1(TXD3/PCINT10)_64") (pintype "bidirectional"))
    )
    (net (code "82") (name "unconnected-(ATMEGA2560-(CLKO{slash}ICP3{slash}INT7)PE7-Pad9)") (class "Default")
      (node (ref "ATMEGA2560") (pin "9") (pinfunction "(CLKO/ICP3/INT7)PE7_9") (pintype "bidirectional"))
    )
    (net (code "83") (name "unconnected-(ATMEGA2560-(ICP1)PD4-Pad47)") (class "Default")
      (node (ref "ATMEGA2560") (pin "47") (pinfunction "(ICP1)PD4_47") (pintype "bidirectional"))
    )
    (net (code "84") (name "unconnected-(ATMEGA2560-(T1)PD6-Pad49)") (class "Default")
      (node (ref "ATMEGA2560") (pin "49") (pinfunction "(T1)PD6_49") (pintype "bidirectional"))
    )
    (net (code "85") (name "unconnected-(ATMEGA2560-(T3{slash}INT6)PE6-Pad8)") (class "Default")
      (node (ref "ATMEGA2560") (pin "8") (pinfunction "(T3/INT6)PE6_8") (pintype "bidirectional"))
    )
    (net (code "86") (name "unconnected-(ATMEGA2560-(TOSC1)PG4-Pad29)") (class "Default")
      (node (ref "ATMEGA2560") (pin "29") (pinfunction "(TOSC1)PG4_29") (pintype "bidirectional"))
    )
    (net (code "87") (name "unconnected-(ATMEGA2560-(TOSC2)PG3-Pad28)") (class "Default")
      (node (ref "ATMEGA2560") (pin "28") (pinfunction "(TOSC2)PG3_28") (pintype "bidirectional"))
    )
    (net (code "88") (name "unconnected-(ATMEGA2560-(XCK0{slash}AIN0)PE2-Pad4)") (class "Default")
      (node (ref "ATMEGA2560") (pin "4") (pinfunction "(XCK0/AIN0)PE2_4") (pintype "bidirectional"))
    )
    (net (code "89") (name "unconnected-(ATMEGA2560-(XCK1)PD5-Pad48)") (class "Default")
      (node (ref "ATMEGA2560") (pin "48") (pinfunction "(XCK1)PD5_48") (pintype "bidirectional"))
    )
    (net (code "90") (name "unconnected-(ATMEGA2560-PH2(XCK2)-Pad14)") (class "Default")
      (node (ref "ATMEGA2560") (pin "14") (pinfunction "PH2(XCK2)_14") (pintype "bidirectional"))
    )
    (net (code "91") (name "unconnected-(ATMEGA2560-PH7(T4)-Pad27)") (class "Default")
      (node (ref "ATMEGA2560") (pin "27") (pinfunction "PH7(T4)_27") (pintype "bidirectional"))
    )
    (net (code "92") (name "unconnected-(ATMEGA2560-PJ2(XCK3{slash}PCINT11)-Pad65)") (class "Default")
      (node (ref "ATMEGA2560") (pin "65") (pinfunction "PJ2(XCK3/PCINT11)_65") (pintype "bidirectional"))
    )
    (net (code "93") (name "unconnected-(ATMEGA2560-PJ3(PCINT12)-Pad66)") (class "Default")
      (node (ref "ATMEGA2560") (pin "66") (pinfunction "PJ3(PCINT12)_66") (pintype "bidirectional"))
    )
    (net (code "94") (name "unconnected-(ATMEGA2560-PJ4(PCINT13)-Pad67)") (class "Default")
      (node (ref "ATMEGA2560") (pin "67") (pinfunction "PJ4(PCINT13)_67") (pintype "bidirectional"))
    )
    (net (code "95") (name "unconnected-(ATMEGA2560-PJ5(PCINT14)-Pad68)") (class "Default")
      (node (ref "ATMEGA2560") (pin "68") (pinfunction "PJ5(PCINT14)_68") (pintype "bidirectional"))
    )
    (net (code "96") (name "unconnected-(ATMEGA2560-PJ6(PCINT15)-Pad69)") (class "Default")
      (node (ref "ATMEGA2560") (pin "69") (pinfunction "PJ6(PCINT15)_69") (pintype "bidirectional"))
    )
    (net (code "97") (name "unconnected-(ATMEGA2560-PJ7-Pad79)") (class "Default")
      (node (ref "ATMEGA2560") (pin "79") (pinfunction "PJ7_79") (pintype "bidirectional"))
    )
    (net (code "98") (name "unconnected-(SERIAL1-CTS-Pad5)") (class "Default")
      (node (ref "SERIAL1") (pin "5") (pinfunction "CTS_5") (pintype "passive"))
    )
  )
)
